# Receiver-2_4GHz.net
KiCad netlist of a schematic drawn in Altium Designer
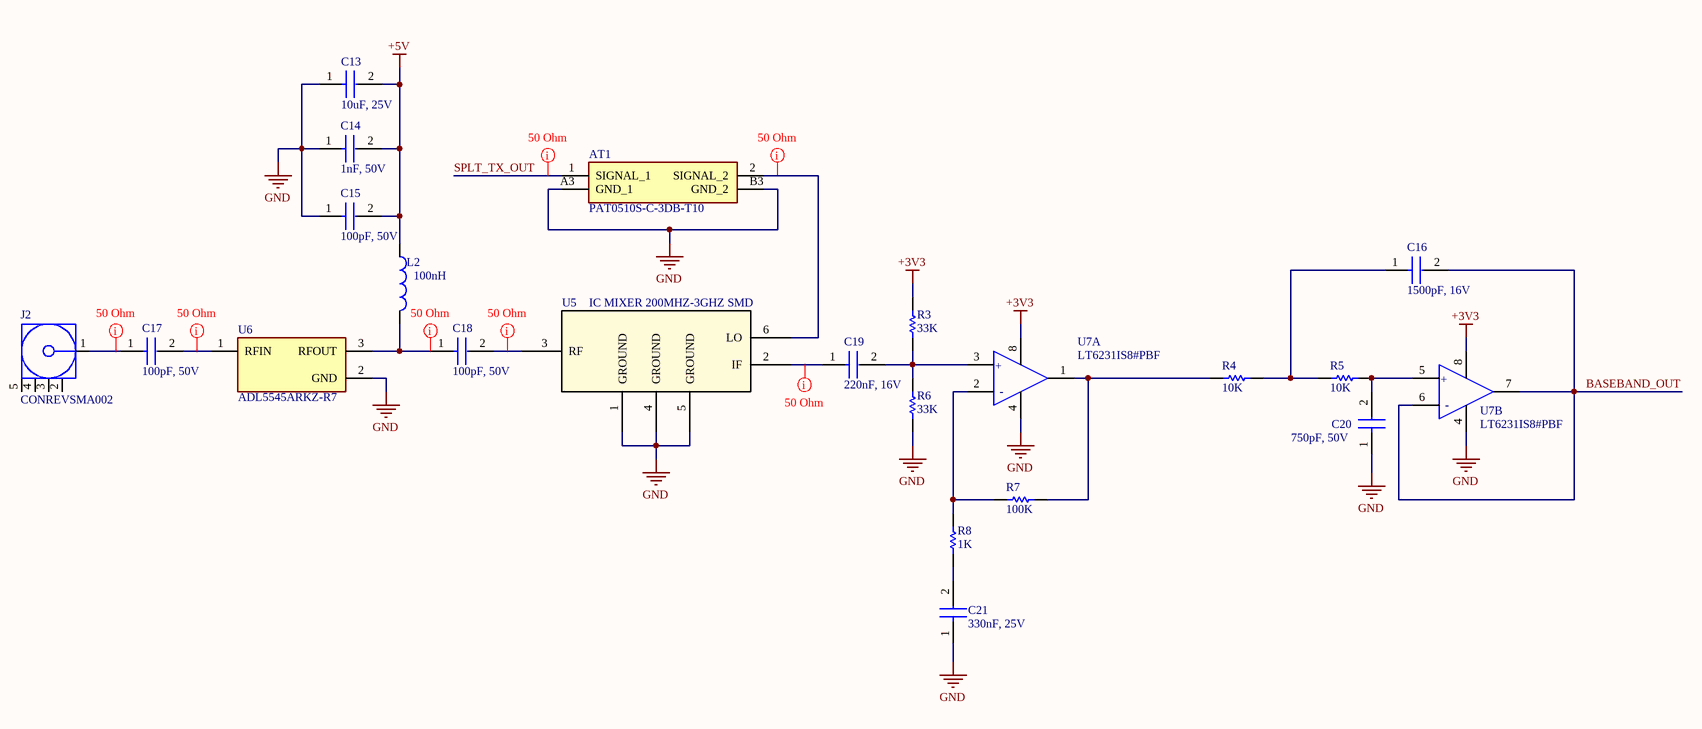
[diagram p0: Receiver-2.4GHz.SchDoc]

(export (version "E")
  (design (tool "Eeschema 10.0.6"))
  (components
    (comp (ref "AT1")
      (value "PAT0510S-C-3DB-T10")
      (footprint "PAT0510SC3DBT10")
      (description "Fixed Attenuator, 0MHz Min, 10000MHz Max")
      (fields (field (name "MANUFACTURER") "Susumu"))
      (libsource (lib "FMCW-Radar-v1") (part "PAT0510S-C-3DB-T10"))
    )
    (comp (ref "C13")
      (value "10uF, 25V")
      (footprint "CAP_CL31_SAM")
      (fields
        (field (name "MANUFACTURER") "Samsung")
        (field (name "MANUFACTURER PART NUMBER") "CL31B106KAHNNNE")
      )
      (libsource (lib "FMCW-Radar-v1") (part "CL31B106KAHNNNE"))
    )
    (comp (ref "C14")
      (value "1nF, 50V")
      (footprint "FP-0603-L_1_6_0_15-W_0_81-IPC_C")
      (fields
        (field (name "MANUFACTURER") "Kyocera AVX")
        (field (name "MANUFACTURER PART NUMBER") "06035A102JAT2A")
      )
      (libsource (lib "FMCW-Radar-v1") (part "06035A102JAT2A"))
    )
    (comp (ref "C15")
      (value "100pF, 50V")
      (footprint "CAPC17595_87N_KEM")
      (fields
        (field (name "MANUFACTURER") "KEMET")
        (field (name "MANUFACTURER PART NUMBER") "C0603C101J5GACTU")
      )
      (libsource (lib "FMCW-Radar-v1") (part "C0603C101J5GACTU"))
    )
    (comp (ref "C16")
      (value "1500pF, 16V")
      (footprint "CAPC1005X55N")
      (fields
        (field (name "MANUFACTURER") "KEMET")
        (field (name "MANUFACTURER PART NUMBER") "C0402C152F4HACAUTO")
      )
      (libsource (lib "FMCW-Radar-v1") (part "C0402C152F4HACAUTO"))
    )
    (comp (ref "C17")
      (value "100pF, 50V")
      (footprint "CAP_CC0402_YAG")
      (fields
        (field (name "MANUFACTURER") "Yageo")
        (field (name "MANUFACTURER PART NUMBER") "CC0402JRNPO9BN101")
      )
      (libsource (lib "FMCW-Radar-v1") (part "CC0402JRNPO9BN101"))
    )
    (comp (ref "C18")
      (value "100pF, 50V")
      (footprint "CAP_CC0402_YAG")
      (fields
        (field (name "MANUFACTURER") "Yageo")
        (field (name "MANUFACTURER PART NUMBER") "CC0402JRNPO9BN101")
      )
      (libsource (lib "FMCW-Radar-v1") (part "CC0402JRNPO9BN101"))
    )
    (comp (ref "C19")
      (value "220nF, 16V")
      (footprint "FP-GRM155-0_05-IPC_C")
      (fields
        (field (name "MANUFACTURER") "Murata")
        (field (name "MANUFACTURER PART NUMBER") "GRM155R71C224KA12D")
      )
      (libsource (lib "FMCW-Radar-v1") (part "GRM155R71C224KA12D"))
    )
    (comp (ref "C20")
      (value "750pF, 50V")
      (footprint "CAPC1005X55N")
      (fields
        (field (name "MANUFACTURER") "Murata")
        (field (name "MANUFACTURER PART NUMBER") "GCM1555C1H751FA16D")
      )
      (libsource (lib "FMCW-Radar-v1") (part "GCM1555C1H751FA16D"))
    )
    (comp (ref "C21")
      (value "330nF, 25V")
      (footprint "CAP_CC0603_YAG-M")
      (fields
        (field (name "MANUFACTURER") "Yageo")
        (field (name "MANUFACTURER PART NUMBER") "CC0603JRX7R8BB334")
      )
      (libsource (lib "FMCW-Radar-v1") (part "CC0603JRX7R8BB334"))
    )
    (comp (ref "J2")
      (value "CONREVSMA002")
      (footprint "CON-REVSMA-RA")
      (description "RF SMA Connector")
      (fields (field (name "MANUFACTURER") "Linx"))
      (libsource (lib "FMCW-Radar-v1") (part "CONREVSMA002"))
    )
    (comp (ref "L2")
      (value "100nH")
      (footprint "INDC1608X95N")
      (description "General Purpose Inductor, 0.1uH, 5%, 1 Element, Air-Core, SMD, 0603")
      (fields
        (field (name "MANUFACTURER") "Murata")
        (field (name "MANUFACTURER PART NUMBER") "LQG18HNR10J00D")
      )
      (libsource (lib "FMCW-Radar-v1") (part "LQG18HNR10J00D"))
    )
    (comp (ref "R3")
      (value "33K")
      (footprint "RESC1005X40N")
      (fields
        (field (name "MANUFACTURER") "TE Connectivity")
        (field (name "MANUFACTURER PART NUMBER") "CRGCQ0402F33K")
      )
      (libsource (lib "FMCW-Radar-v1") (part "CRGCQ0402F33K"))
    )
    (comp (ref "R4")
      (value "10K")
      (footprint "RESC1005X37N")
      (fields
        (field (name "MANUFACTURER") "Yageo")
        (field (name "MANUFACTURER PART NUMBER") "AC0402FR-0710KL")
        (field (name "TOLERANCE") "1%")
      )
      (libsource (lib "FMCW-Radar-v1") (part "AC0402FR-0710KL"))
    )
    (comp (ref "R5")
      (value "10K")
      (footprint "RESC1005X37N")
      (fields
        (field (name "MANUFACTURER") "Yageo")
        (field (name "MANUFACTURER PART NUMBER") "AC0402FR-0710KL")
        (field (name "TOLERANCE") "1%")
      )
      (libsource (lib "FMCW-Radar-v1") (part "AC0402FR-0710KL"))
    )
    (comp (ref "R6")
      (value "33K")
      (footprint "RESC1005X40N")
      (fields
        (field (name "MANUFACTURER") "TE Connectivity")
        (field (name "MANUFACTURER PART NUMBER") "CRGCQ0402F33K")
      )
      (libsource (lib "FMCW-Radar-v1") (part "CRGCQ0402F33K"))
    )
    (comp (ref "R7")
      (value "100K")
      (footprint "RESC1005X40N")
      (fields
        (field (name "MANUFACTURER") "Yageo")
        (field (name "MANUFACTURER PART NUMBER") "RC0402FR-07300KL")
        (field (name "TOLERANCE") "1%")
      )
      (libsource (lib "FMCW-Radar-v1") (part "RC0402FR-07300KL"))
    )
    (comp (ref "R8")
      (value "1K")
      (footprint "FP-RC0402-0_4-IPC_C")
      (fields
        (field (name "MANUFACTURER") "Yageo")
        (field (name "MANUFACTURER PART NUMBER") "RC0402FR-071KL")
        (field (name "TOLERANCE") "1%")
      )
      (libsource (lib "FMCW-Radar-v1") (part "RC0402FR-071KL"))
    )
    (comp (ref "U5")
      (value "IC MIXER 200MHZ-3GHZ SMD")
      (footprint "CD542_MNC")
      (libsource (lib "FMCW-Radar-v1") (part "ADE-30+"))
    )
    (comp (ref "U6")
      (value "ADL5545ARKZ-R7")
      (footprint "ADL5545ARKZ-R7")
      (description "Wide Band Medium Power Amplifier, 30MHz Min, 6000MHz Max, 1 Func, BIPolar")
      (fields (field (name "MANUFACTURER") "Analog Devices"))
      (libsource (lib "FMCW-Radar-v1") (part "ADL5545ARKZ-R7"))
    )
    (comp (ref "U7")
      (value "LT6231IS8#PBF")
      (footprint "FP-LT6231IS8#PBF-IPC_C")
      (description "Operational Amplifier, 2 Func, 550uV Offset-Max, PDSO8")
      (fields (field (name "MANUFACTURER") "Analog Devices / Linear Technology"))
      (libsource (lib "FMCW-Radar-v1") (part "LT6231IS8#PBF"))
    )
  )
  (nets
    (net (code "1") (name "+3V3") (class "Default")
      (node (ref "R3") (pin "2") (pinfunction "2_2") (pintype "passive"))
      (node (ref "U7") (pin "8") (pinfunction "V+_8") (pintype "power_in"))
    )
    (net (code "2") (name "+5V") (class "Default")
      (node (ref "C13") (pin "2") (pinfunction "2_2") (pintype "passive"))
      (node (ref "C14") (pin "2") (pinfunction "2_2") (pintype "passive"))
      (node (ref "C15") (pin "2") (pinfunction "2_2") (pintype "passive"))
      (node (ref "L2") (pin "1") (pinfunction "1_1") (pintype "passive"))
    )
    (net (code "3") (name "/BASEBAND_OUT") (class "Default")
      (node (ref "C16") (pin "2") (pinfunction "2_2") (pintype "passive"))
      (node (ref "U7") (pin "6") (pinfunction "-IN_B_6") (pintype "tri_state"))
      (node (ref "U7") (pin "7") (pinfunction "OUT_B_7") (pintype "passive"))
    )
    (net (code "4") (name "/SPLT_TX_OUT") (class "Default")
      (node (ref "AT1") (pin "1") (pinfunction "SIGNAL_1_1") (pintype "passive"))
    )
    (net (code "5") (name "GND") (class "Default")
      (node (ref "AT1") (pin "A3") (pinfunction "GND_1_A3") (pintype "passive"))
      (node (ref "AT1") (pin "B3") (pinfunction "GND_2_B3") (pintype "passive"))
      (node (ref "C13") (pin "1") (pinfunction "1_1") (pintype "passive"))
      (node (ref "C14") (pin "1") (pinfunction "1_1") (pintype "passive"))
      (node (ref "C15") (pin "1") (pinfunction "1_1") (pintype "passive"))
      (node (ref "C20") (pin "1") (pinfunction "1_1") (pintype "passive"))
      (node (ref "C21") (pin "1") (pinfunction "1_1") (pintype "passive"))
      (node (ref "R6") (pin "1") (pinfunction "1_1") (pintype "passive"))
      (node (ref "U5") (pin "1") (pinfunction "GROUND_1") (pintype "power_in"))
      (node (ref "U5") (pin "4") (pinfunction "GROUND_4") (pintype "power_in"))
      (node (ref "U5") (pin "5") (pinfunction "GROUND_5") (pintype "power_in"))
      (node (ref "U6") (pin "2") (pinfunction "GND_2") (pintype "passive"))
      (node (ref "U7") (pin "4") (pinfunction "V-_4") (pintype "power_in"))
    )
    (net (code "6") (name "Net-(AT1-SIGNAL_2)") (class "Default")
      (node (ref "AT1") (pin "2") (pinfunction "SIGNAL_2_2") (pintype "passive"))
      (node (ref "U5") (pin "6") (pinfunction "LO_6") (pintype "passive"))
    )
    (net (code "7") (name "Net-(C16-Pad1)") (class "Default")
      (node (ref "C16") (pin "1") (pinfunction "1_1") (pintype "passive"))
      (node (ref "R4") (pin "2") (pinfunction "2_2") (pintype "passive"))
      (node (ref "R5") (pin "1") (pinfunction "1_1") (pintype "passive"))
    )
    (net (code "8") (name "Net-(C21-Pad2)") (class "Default")
      (node (ref "C21") (pin "2") (pinfunction "2_2") (pintype "passive"))
      (node (ref "R8") (pin "2") (pinfunction "2_2") (pintype "passive"))
    )
    (net (code "9") (name "Net-(J2-Signal)") (class "Default")
      (node (ref "C17") (pin "1") (pinfunction "1_1") (pintype "passive"))
      (node (ref "J2") (pin "1") (pinfunction "Signal_1") (pintype "passive"))
    )
    (net (code "10") (name "Net-(U5-IF)") (class "Default")
      (node (ref "C19") (pin "1") (pinfunction "1_1") (pintype "passive"))
      (node (ref "U5") (pin "2") (pinfunction "IF_2") (pintype "passive"))
    )
    (net (code "11") (name "Net-(U5-RF)") (class "Default")
      (node (ref "C18") (pin "2") (pinfunction "2_2") (pintype "passive"))
      (node (ref "U5") (pin "3") (pinfunction "RF_3") (pintype "passive"))
    )
    (net (code "12") (name "Net-(U6-RFIN)") (class "Default")
      (node (ref "C17") (pin "2") (pinfunction "2_2") (pintype "passive"))
      (node (ref "U6") (pin "1") (pinfunction "RFIN_1") (pintype "passive"))
    )
    (net (code "13") (name "Net-(U6-RFOUT)") (class "Default")
      (node (ref "C18") (pin "1") (pinfunction "1_1") (pintype "passive"))
      (node (ref "L2") (pin "2") (pinfunction "2_2") (pintype "passive"))
      (node (ref "U6") (pin "3") (pinfunction "RFOUT_3") (pintype "passive"))
    )
    (net (code "14") (name "Net-(U7A-+IN_A)") (class "Default")
      (node (ref "C19") (pin "2") (pinfunction "2_2") (pintype "passive"))
      (node (ref "R3") (pin "1") (pinfunction "1_1") (pintype "passive"))
      (node (ref "R6") (pin "2") (pinfunction "2_2") (pintype "passive"))
      (node (ref "U7") (pin "3") (pinfunction "+IN_A_3") (pintype "tri_state"))
    )
    (net (code "15") (name "Net-(U7A--IN_A)") (class "Default")
      (node (ref "R7") (pin "1") (pinfunction "1_1") (pintype "passive"))
      (node (ref "R8") (pin "1") (pinfunction "1_1") (pintype "passive"))
      (node (ref "U7") (pin "2") (pinfunction "-IN_A_2") (pintype "tri_state"))
    )
    (net (code "16") (name "Net-(U7A-OUT_A)") (class "Default")
      (node (ref "R4") (pin "1") (pinfunction "1_1") (pintype "passive"))
      (node (ref "R7") (pin "2") (pinfunction "2_2") (pintype "passive"))
      (node (ref "U7") (pin "1") (pinfunction "OUT_A_1") (pintype "passive"))
    )
    (net (code "17") (name "Net-(U7B-IN_B)") (class "Default")
      (node (ref "C20") (pin "2") (pinfunction "2_2") (pintype "passive"))
      (node (ref "R5") (pin "2") (pinfunction "2_2") (pintype "passive"))
      (node (ref "U7") (pin "5") (pinfunction "IN_B_5") (pintype "tri_state"))
    )
    (net (code "18") (name "unconnected-(J2-GND-Pad2)") (class "Default")
      (node (ref "J2") (pin "2") (pinfunction "GND_2") (pintype "power_in"))
    )
    (net (code "19") (name "unconnected-(J2-GND-Pad3)") (class "Default")
      (node (ref "J2") (pin "3") (pinfunction "GND_3") (pintype "power_in"))
    )
    (net (code "20") (name "unconnected-(J2-GND-Pad4)") (class "Default")
      (node (ref "J2") (pin "4") (pinfunction "GND_4") (pintype "power_in"))
    )
    (net (code "21") (name "unconnected-(J2-GND-Pad5)") (class "Default")
      (node (ref "J2") (pin "5") (pinfunction "GND_5") (pintype "power_in"))
    )
  )
)
